# dualshock_c64_adapter.net
KiCad netlist of a schematic drawn in EAGLE
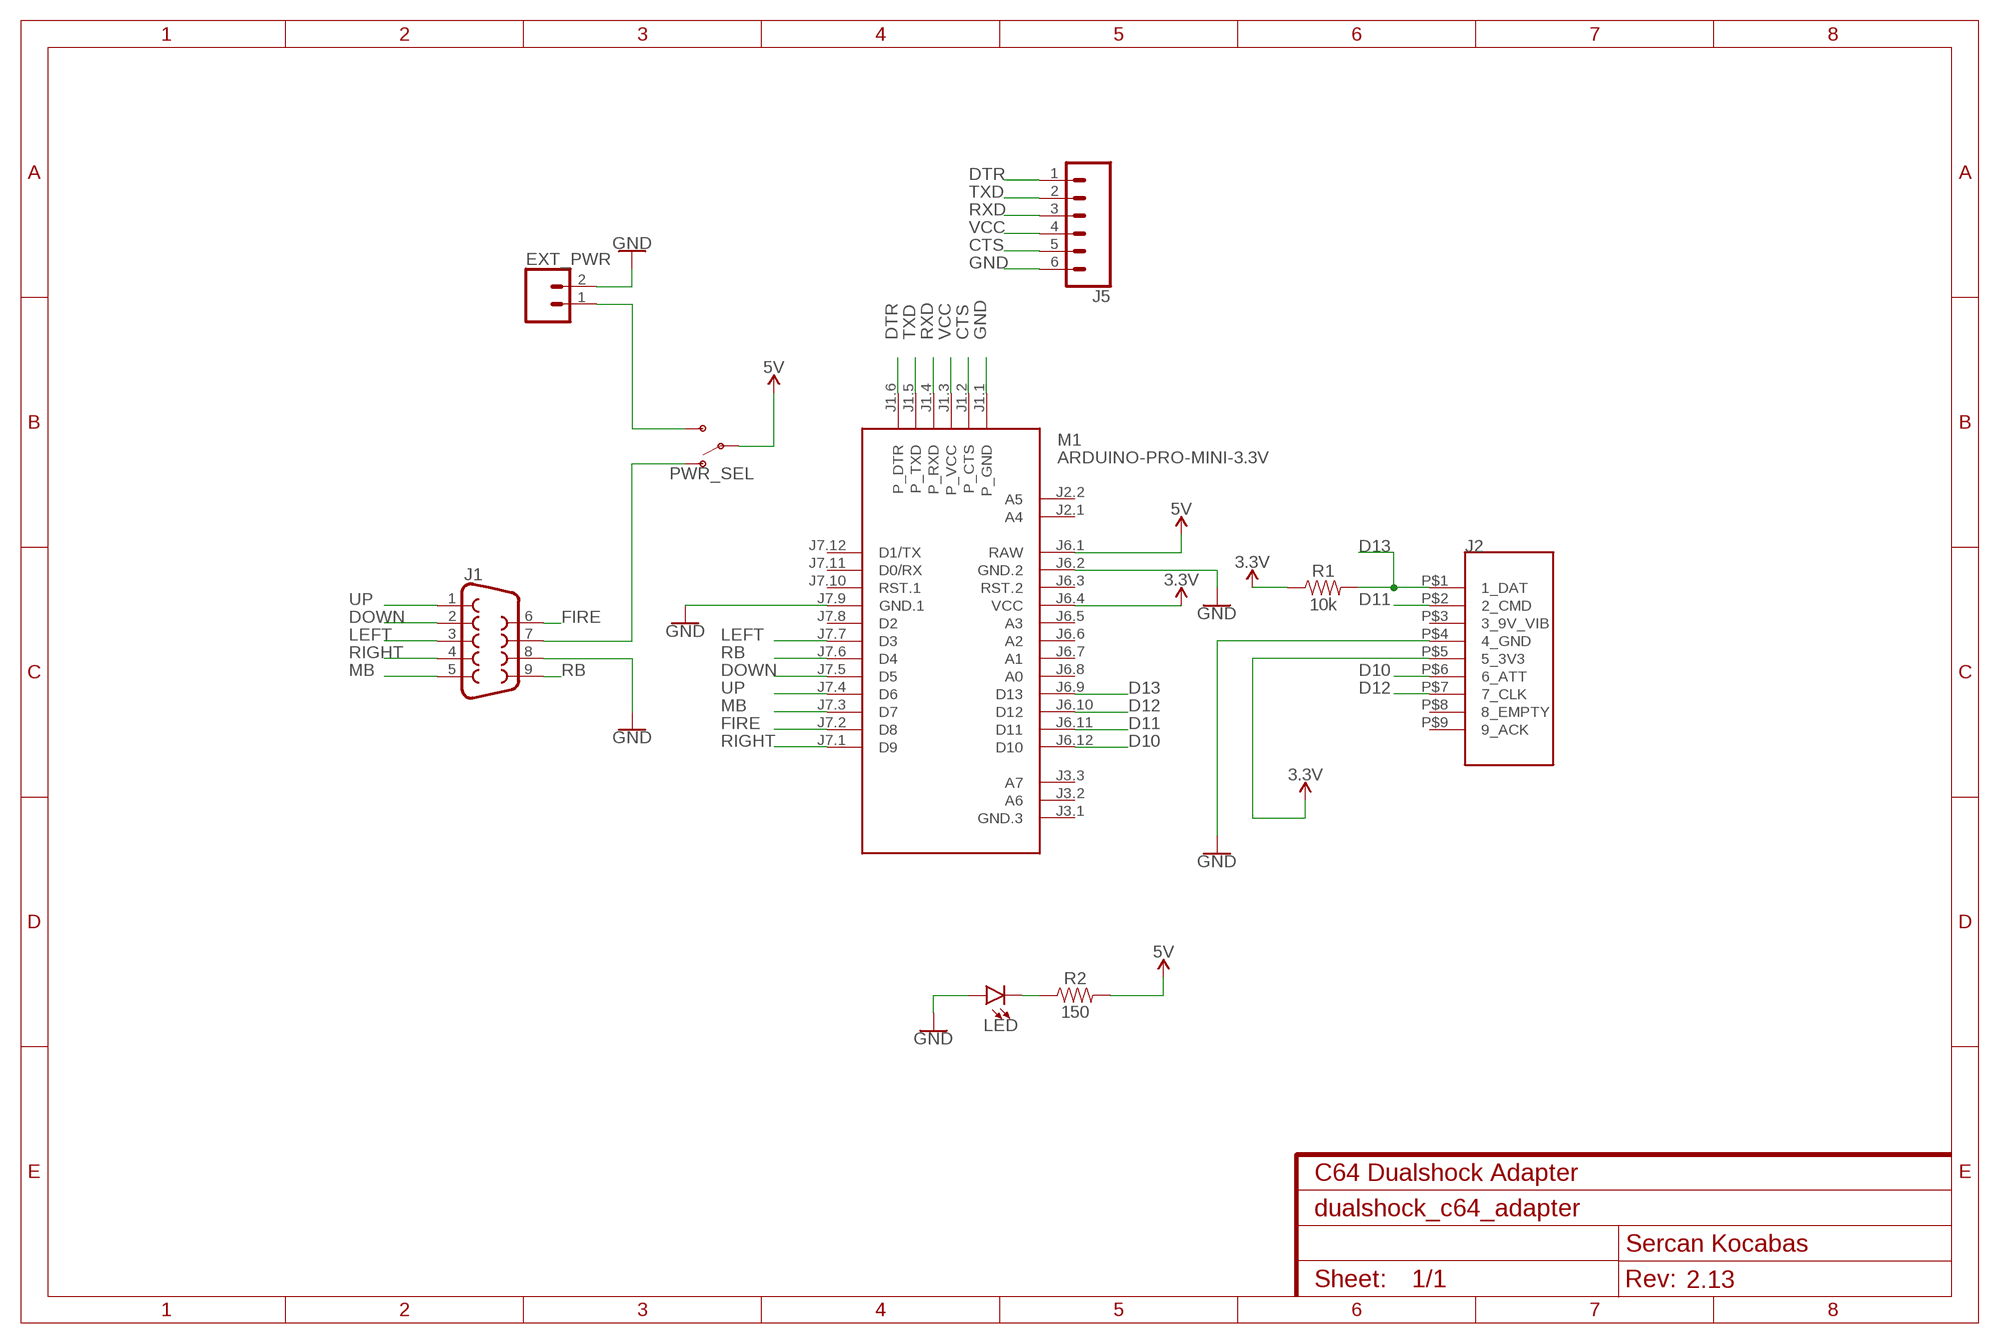
[diagram p0: schematic, sheet 1]

(export (version "E")
  (design (tool "Eeschema 10.0.6"))
  (components
    (comp (ref "EXT_PWR")
      (value "CONN_02")
      (footprint "eagle-import:1X02")
      (libsource (lib "eagle-import") (part "CONN_02"))
    )
    (comp (ref "J1")
      (value "DB9FEMALE")
      (footprint "eagle-import:DB9")
      (libsource (lib "eagle-import") (part "DB9FEMALE"))
    )
    (comp (ref "J2")
      (value "PS2_DUALSHOCK")
      (footprint "eagle-import:PS2_DUALSHOCK")
      (libsource (lib "eagle-import") (part "PS2_DUALSHOCK"))
    )
    (comp (ref "J5")
      (value "CONN_06NO_SILK_FEMALE_PTH")
      (footprint "eagle-import:1X06_NO_SILK")
      (libsource (lib "eagle-import") (part "CONN_06NO_SILK_FEMALE_PTH"))
    )
    (comp (ref "LED")
      (value "LED5MM")
      (footprint "eagle-import:LED_5MM")
      (libsource (lib "eagle-import") (part "LED5MM"))
    )
    (comp (ref "M1")
      (value "ARDUINO-PRO-MINI-3.3V")
      (footprint "eagle-import:ARDUINO-PRO-MINI")
      (libsource (lib "eagle-import") (part "ARDUINO-PRO-MINI-3.3V"))
    )
    (comp (ref "PWR_SEL")
      (value "SWITCH-SPDT-PTH-11.6X4.0MM")
      (footprint "eagle-import:SWITCH_SPDT_PTH_11.6X4.0MM")
      (libsource (lib "eagle-import") (part "SWITCH-SPDT-PTH-11.6X4.0MM"))
    )
    (comp (ref "R1")
      (value "10k")
      (footprint "eagle-import:AXIAL-0.3")
      (libsource (lib "eagle-import") (part "10KOHM-HORIZ-1/4W-1%"))
    )
    (comp (ref "R2")
      (value "150")
      (footprint "eagle-import:AXIAL-0.3")
      (libsource (lib "eagle-import") (part "10KOHM-HORIZ-1/4W-1%"))
    )
  )
  (nets
    (net (code "1") (name "/CTS") (class "Default")
      (node (ref "J5") (pin "5") (pinfunction "5_5") (pintype "passive"))
      (node (ref "M1") (pin "J1.2") (pinfunction "P_CTS_J1.2") (pintype "bidirectional"))
    )
    (net (code "2") (name "/D10") (class "Default")
      (node (ref "J2") (pin "P$6") (pinfunction "6_ATT_P$6") (pintype "bidirectional"))
      (node (ref "M1") (pin "J6.12") (pinfunction "D10_J6.12") (pintype "bidirectional"))
    )
    (net (code "3") (name "/D11") (class "Default")
      (node (ref "J2") (pin "P$2") (pinfunction "2_CMD_P$2") (pintype "bidirectional"))
      (node (ref "M1") (pin "J6.11") (pinfunction "D11_J6.11") (pintype "bidirectional"))
    )
    (net (code "4") (name "/D12") (class "Default")
      (node (ref "J2") (pin "P$7") (pinfunction "7_CLK_P$7") (pintype "bidirectional"))
      (node (ref "M1") (pin "J6.10") (pinfunction "D12_J6.10") (pintype "bidirectional"))
    )
    (net (code "5") (name "/D13") (class "Default")
      (node (ref "J2") (pin "P$1") (pinfunction "1_DAT_P$1") (pintype "bidirectional"))
      (node (ref "M1") (pin "J6.9") (pinfunction "D13_J6.9") (pintype "bidirectional"))
      (node (ref "R1") (pin "P$2") (pinfunction "2_P$2") (pintype "passive"))
    )
    (net (code "6") (name "/DOWN") (class "Default")
      (node (ref "J1") (pin "2") (pinfunction "2_2") (pintype "passive"))
      (node (ref "M1") (pin "J7.5") (pinfunction "D5_J7.5") (pintype "bidirectional"))
    )
    (net (code "7") (name "/DTR") (class "Default")
      (node (ref "J5") (pin "1") (pinfunction "1_1") (pintype "passive"))
      (node (ref "M1") (pin "J1.6") (pinfunction "P_DTR_J1.6") (pintype "bidirectional"))
    )
    (net (code "8") (name "/FIRE") (class "Default")
      (node (ref "J1") (pin "6") (pinfunction "6_6") (pintype "passive"))
      (node (ref "M1") (pin "J7.2") (pinfunction "D8_J7.2") (pintype "bidirectional"))
    )
    (net (code "9") (name "/LEFT") (class "Default")
      (node (ref "J1") (pin "3") (pinfunction "3_3") (pintype "passive"))
      (node (ref "M1") (pin "J7.7") (pinfunction "D3_J7.7") (pintype "bidirectional"))
    )
    (net (code "10") (name "/MB") (class "Default")
      (node (ref "J1") (pin "5") (pinfunction "5_5") (pintype "passive"))
      (node (ref "M1") (pin "J7.3") (pinfunction "D7_J7.3") (pintype "bidirectional"))
    )
    (net (code "11") (name "/RB") (class "Default")
      (node (ref "J1") (pin "9") (pinfunction "9_9") (pintype "passive"))
      (node (ref "M1") (pin "J7.6") (pinfunction "D4_J7.6") (pintype "bidirectional"))
    )
    (net (code "12") (name "/RIGHT") (class "Default")
      (node (ref "J1") (pin "4") (pinfunction "4_4") (pintype "passive"))
      (node (ref "M1") (pin "J7.1") (pinfunction "D9_J7.1") (pintype "bidirectional"))
    )
    (net (code "13") (name "/RXD") (class "Default")
      (node (ref "J5") (pin "3") (pinfunction "3_3") (pintype "passive"))
      (node (ref "M1") (pin "J1.4") (pinfunction "P_RXD_J1.4") (pintype "bidirectional"))
    )
    (net (code "14") (name "/TXD") (class "Default")
      (node (ref "J5") (pin "2") (pinfunction "2_2") (pintype "passive"))
      (node (ref "M1") (pin "J1.5") (pinfunction "P_TXD_J1.5") (pintype "bidirectional"))
    )
    (net (code "15") (name "/UP") (class "Default")
      (node (ref "J1") (pin "1") (pinfunction "1_1") (pintype "passive"))
      (node (ref "M1") (pin "J7.4") (pinfunction "D6_J7.4") (pintype "bidirectional"))
    )
    (net (code "16") (name "/VCC") (class "Default")
      (node (ref "J5") (pin "4") (pinfunction "4_4") (pintype "passive"))
      (node (ref "M1") (pin "J1.3") (pinfunction "P_VCC_J1.3") (pintype "bidirectional"))
    )
    (net (code "17") (name "3.3V") (class "Default")
      (node (ref "J2") (pin "P$5") (pinfunction "5_3V3_P$5") (pintype "bidirectional"))
      (node (ref "M1") (pin "J6.4") (pinfunction "VCC_J6.4") (pintype "power_in"))
      (node (ref "R1") (pin "P$1") (pinfunction "1_P$1") (pintype "passive"))
    )
    (net (code "18") (name "5V") (class "Default")
      (node (ref "M1") (pin "J6.1") (pinfunction "RAW_J6.1") (pintype "power_in"))
      (node (ref "PWR_SEL") (pin "2") (pinfunction "P_2") (pintype "passive"))
      (node (ref "R2") (pin "P$2") (pinfunction "2_P$2") (pintype "passive"))
    )
    (net (code "19") (name "GND") (class "Default")
      (node (ref "EXT_PWR") (pin "2") (pinfunction "2_2") (pintype "passive"))
      (node (ref "J1") (pin "8") (pinfunction "8_8") (pintype "passive"))
      (node (ref "J2") (pin "P$4") (pinfunction "4_GND_P$4") (pintype "bidirectional"))
      (node (ref "J5") (pin "6") (pinfunction "6_6") (pintype "passive"))
      (node (ref "LED") (pin "A") (pinfunction "A_A") (pintype "passive"))
      (node (ref "M1") (pin "J1.1") (pinfunction "P_GND_J1.1") (pintype "bidirectional"))
      (node (ref "M1") (pin "J6.2") (pinfunction "GND.2_J6.2") (pintype "power_in"))
      (node (ref "M1") (pin "J7.9") (pinfunction "GND.1_J7.9") (pintype "power_in"))
    )
    (net (code "20") (name "Net-(LED-C)") (class "Default")
      (node (ref "LED") (pin "K") (pinfunction "C_K") (pintype "passive"))
      (node (ref "R2") (pin "P$1") (pinfunction "1_P$1") (pintype "passive"))
    )
    (net (code "21") (name "Net-(PWR_SEL-O)") (class "Default")
      (node (ref "J1") (pin "7") (pinfunction "7_7") (pintype "passive"))
      (node (ref "PWR_SEL") (pin "1") (pinfunction "O_1") (pintype "passive"))
    )
    (net (code "22") (name "Net-(PWR_SEL-S)") (class "Default")
      (node (ref "EXT_PWR") (pin "1") (pinfunction "1_1") (pintype "passive"))
      (node (ref "PWR_SEL") (pin "3") (pinfunction "S_3") (pintype "passive"))
    )
    (net (code "23") (name "unconnected-(J2-3_9V_VIB-PadP$3)") (class "Default")
      (node (ref "J2") (pin "P$3") (pinfunction "3_9V_VIB_P$3") (pintype "bidirectional"))
    )
    (net (code "24") (name "unconnected-(J2-8_EMPTY-PadP$8)") (class "Default")
      (node (ref "J2") (pin "P$8") (pinfunction "8_EMPTY_P$8") (pintype "bidirectional"))
    )
    (net (code "25") (name "unconnected-(J2-9_ACK-PadP$9)") (class "Default")
      (node (ref "J2") (pin "P$9") (pinfunction "9_ACK_P$9") (pintype "bidirectional"))
    )
    (net (code "26") (name "unconnected-(M1-A0-PadJ6.8)") (class "Default")
      (node (ref "M1") (pin "J6.8") (pinfunction "A0_J6.8") (pintype "bidirectional"))
    )
    (net (code "27") (name "unconnected-(M1-A1-PadJ6.7)") (class "Default")
      (node (ref "M1") (pin "J6.7") (pinfunction "A1_J6.7") (pintype "bidirectional"))
    )
    (net (code "28") (name "unconnected-(M1-A2-PadJ6.6)") (class "Default")
      (node (ref "M1") (pin "J6.6") (pinfunction "A2_J6.6") (pintype "bidirectional"))
    )
    (net (code "29") (name "unconnected-(M1-A3-PadJ6.5)") (class "Default")
      (node (ref "M1") (pin "J6.5") (pinfunction "A3_J6.5") (pintype "bidirectional"))
    )
    (net (code "30") (name "unconnected-(M1-A4-PadJ2.1)") (class "Default")
      (node (ref "M1") (pin "J2.1") (pinfunction "A4_J2.1") (pintype "bidirectional"))
    )
    (net (code "31") (name "unconnected-(M1-A5-PadJ2.2)") (class "Default")
      (node (ref "M1") (pin "J2.2") (pinfunction "A5_J2.2") (pintype "bidirectional"))
    )
    (net (code "32") (name "unconnected-(M1-A6-PadJ3.2)") (class "Default")
      (node (ref "M1") (pin "J3.2") (pinfunction "A6_J3.2") (pintype "bidirectional"))
    )
    (net (code "33") (name "unconnected-(M1-A7-PadJ3.3)") (class "Default")
      (node (ref "M1") (pin "J3.3") (pinfunction "A7_J3.3") (pintype "bidirectional"))
    )
    (net (code "34") (name "unconnected-(M1-D0{slash}RX-PadJ7.11)") (class "Default")
      (node (ref "M1") (pin "J7.11") (pinfunction "D0/RX_J7.11") (pintype "bidirectional"))
    )
    (net (code "35") (name "unconnected-(M1-D1{slash}TX-PadJ7.12)") (class "Default")
      (node (ref "M1") (pin "J7.12") (pinfunction "D1/TX_J7.12") (pintype "bidirectional"))
    )
    (net (code "36") (name "unconnected-(M1-D2-PadJ7.8)") (class "Default")
      (node (ref "M1") (pin "J7.8") (pinfunction "D2_J7.8") (pintype "bidirectional"))
    )
    (net (code "37") (name "unconnected-(M1-GND.3-PadJ3.1)") (class "Default")
      (node (ref "M1") (pin "J3.1") (pinfunction "GND.3_J3.1") (pintype "bidirectional"))
    )
    (net (code "38") (name "unconnected-(M1-RST.1-PadJ7.10)") (class "Default")
      (node (ref "M1") (pin "J7.10") (pinfunction "RST.1_J7.10") (pintype "bidirectional"))
    )
    (net (code "39") (name "unconnected-(M1-RST.2-PadJ6.3)") (class "Default")
      (node (ref "M1") (pin "J6.3") (pinfunction "RST.2_J6.3") (pintype "bidirectional"))
    )
  )
)
